# Temp_Sense.net
KiCad netlist of a schematic drawn in Altium Designer
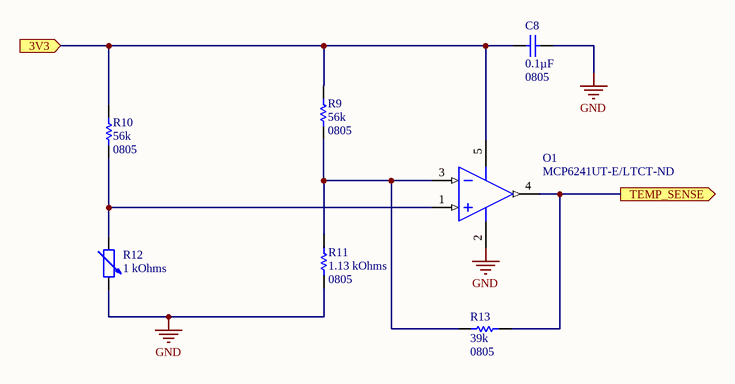
[diagram p0: Temp Sense.SchDoc]

(export (version "E")
  (design (tool "Eeschema 10.0.6"))
  (components
    (comp (ref "C8")
      (value "C0805C104K5RACTU")
      (footprint "CAP0805")
      (description "CAP CER 0.1UF 50V X7R 0805")
      (fields
        (field (name "TOLERANCE") "±10%")
        (field (name "CAPACITANCE") "0.1µF")
        (field (name "PACKAGE / CASE") "0805")
      )
      (libsource (lib "Capacitors") (part "C0805C104K5RACTU"))
    )
    (comp (ref "O1")
      (value "MCP6241U")
      (footprint "MCP6241U")
      (description "IC OPAMP GP 550KHZ RRO SC70-5")
      (fields (field (name "SUPPLIER PART NUMBER 1") "MCP6241UT-E/LTCT-ND"))
      (libsource (lib "Operational_Amplifiers") (part "MCP6241U"))
    )
    (comp (ref "R9")
      (value "RC0805FR-0756KL")
      (footprint "RES0805")
      (description "RES SMD 56K OHM 1% 1/8W 0805")
      (fields
        (field (name "TOLERANCE") "±1%")
        (field (name "RESISTANCE") "56k")
        (field (name "PACKAGE / CASE") "0805")
      )
      (libsource (lib "Resistors") (part "RC0805FR-0756KL"))
    )
    (comp (ref "R10")
      (value "RC0805FR-0756KL")
      (footprint "RES0805")
      (description "RES SMD 56K OHM 1% 1/8W 0805")
      (fields
        (field (name "TOLERANCE") "±1%")
        (field (name "RESISTANCE") "56k")
        (field (name "PACKAGE / CASE") "0805")
      )
      (libsource (lib "Resistors") (part "RC0805FR-0756KL"))
    )
    (comp (ref "R11")
      (value "ERJ-6ENF1131V")
      (footprint "RES0805")
      (description "RES SMD 1.13K OHM 1% 1/8W 0805")
      (fields
        (field (name "TOLERANCE") "±1%")
        (field (name "RESISTANCE") "1.13 kOhms")
        (field (name "SUPPLIER DEVICE PACKAGE") "0805")
      )
      (libsource (lib "Resistors") (part "ERJ-6ENF1131V"))
    )
    (comp (ref "R12")
      (value "G-NICO-001")
      (footprint "G-NICO-001")
      (description "SENSOR TEMP RTD 1.0K OHM SOT23")
      (fields
        (field (name "MANUFACTURER") "TE Connectivity Measurement Specialties")
        (field (name "RESISTANCE") "1 kOhms")
      )
      (libsource (lib "Resistors") (part "G-NICO-001"))
    )
    (comp (ref "R13")
      (value "RC0805FR-0739KL")
      (footprint "RES0805")
      (description "RES SMD 39K OHM 1% 1/8W 0805")
      (fields
        (field (name "TOLERANCE") "±1%")
        (field (name "RESISTANCE") "39k")
        (field (name "PACKAGE / CASE") "0805")
      )
      (libsource (lib "Resistors") (part "RC0805FR-0739KL"))
    )
  )
  (nets
    (net (code "1") (name "/3V3") (class "Default")
      (node (ref "C8") (pin "2") (pinfunction "2_2") (pintype "passive"))
      (node (ref "O1") (pin "5") (pinfunction "V+_5") (pintype "power_in"))
      (node (ref "R10") (pin "2") (pinfunction "2_2") (pintype "passive"))
      (node (ref "R9") (pin "2") (pinfunction "2_2") (pintype "passive"))
    )
    (net (code "2") (name "/TEMP_SENSE") (class "Default")
      (node (ref "O1") (pin "4") (pinfunction "OUT_4") (pintype "output"))
      (node (ref "R13") (pin "2") (pinfunction "2_2") (pintype "passive"))
    )
    (net (code "3") (name "GND") (class "Default")
      (node (ref "C8") (pin "1") (pinfunction "1_1") (pintype "passive"))
      (node (ref "O1") (pin "2") (pinfunction "V-_2") (pintype "power_in"))
      (node (ref "R11") (pin "1") (pinfunction "1_1") (pintype "passive"))
      (node (ref "R12") (pin "2") (pinfunction "2_2") (pintype "passive"))
    )
    (net (code "4") (name "Net-(O1-IN+)") (class "Default")
      (node (ref "O1") (pin "1") (pinfunction "IN+_1") (pintype "input"))
      (node (ref "R10") (pin "1") (pinfunction "1_1") (pintype "passive"))
      (node (ref "R12") (pin "1") (pinfunction "1_1") (pintype "passive"))
    )
    (net (code "5") (name "Net-(O1-IN-)") (class "Default")
      (node (ref "O1") (pin "3") (pinfunction "IN-_3") (pintype "input"))
      (node (ref "R11") (pin "2") (pinfunction "2_2") (pintype "passive"))
      (node (ref "R13") (pin "1") (pinfunction "1_1") (pintype "passive"))
      (node (ref "R9") (pin "1") (pinfunction "1_1") (pintype "passive"))
    )
  )
)
